# 555_module_throu.net
KiCad netlist of a schematic drawn in EAGLE
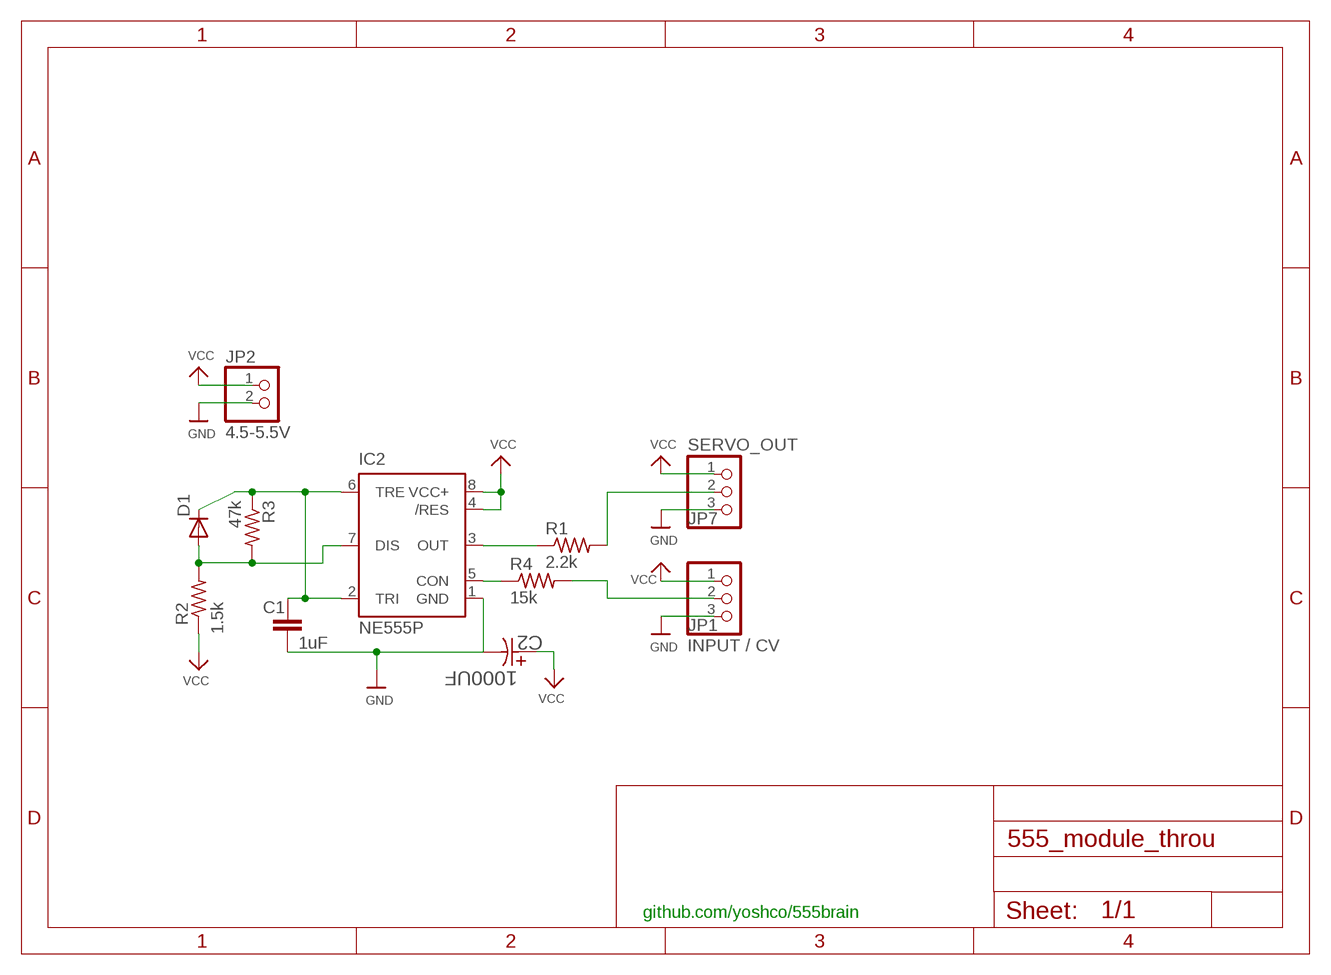
[diagram p0: schematic, sheet 1]

(export (version "E")
  (design (tool "Eeschema 10.0.6"))
  (components
    (comp (ref "C1")
      (value "1uF")
      (footprint "eagle-import:AXIAL-5MM")
      (libsource (lib "eagle-import") (part "CAP_"))
    )
    (comp (ref "C2")
      (value "1000UF")
      (footprint "eagle-import:CAPPR500-1000X3200")
      (fields (field (name "MPN") "EEUFK0J102") (field (name "TOLERANCE") "±20 %"))
      (libsource (lib "eagle-import") (part "EEU-P5.0FK0J102"))
    )
    (comp (ref "D1")
      (value "1N4004")
      (footprint "eagle-import:DO41-10")
      (libsource (lib "eagle-import") (part "1N4004"))
    )
    (comp (ref "IC2")
      (value "NE555P")
      (footprint "eagle-import:DIL-08")
      (fields (field (name "MF") "Arrow Electronics") (field (name "MPN") "NE555N"))
      (libsource (lib "eagle-import") (part "NE555P"))
    )
    (comp (ref "JP1")
      (value "INPUT / CV")
      (footprint "eagle-import:1X03")
      (libsource (lib "eagle-import") (part "PINHD-1X3"))
    )
    (comp (ref "JP2")
      (value "4.5-5.5V")
      (footprint "eagle-import:1X02_OVAL")
      (libsource (lib "eagle-import") (part "HEADER-1X2"))
    )
    (comp (ref "JP7")
      (value "SERVO_OUT")
      (footprint "eagle-import:1X03")
      (libsource (lib "eagle-import") (part "PINHD-1X3"))
    )
    (comp (ref "R1")
      (value "2.2k")
      (footprint "eagle-import:0204_7")
      (libsource (lib "eagle-import") (part "R-US_0204/7"))
    )
    (comp (ref "R2")
      (value "1.5k")
      (footprint "eagle-import:0204_7")
      (libsource (lib "eagle-import") (part "R-US_0204/7"))
    )
    (comp (ref "R3")
      (value "47k")
      (footprint "eagle-import:0204_7")
      (libsource (lib "eagle-import") (part "R-US_0204/7"))
    )
    (comp (ref "R4")
      (value "15k")
      (footprint "eagle-import:0204_7")
      (libsource (lib "eagle-import") (part "R-US_0204/7"))
    )
  )
  (nets
    (net (code "1") (name "GND") (class "Default")
      (node (ref "C1") (pin "P$2") (pinfunction "2_P$2") (pintype "passive"))
      (node (ref "C2") (pin "2") (pinfunction "2_2") (pintype "passive"))
      (node (ref "IC2") (pin "1") (pinfunction "GND_1") (pintype "power_in"))
      (node (ref "JP1") (pin "3") (pinfunction "3_3") (pintype "passive"))
      (node (ref "JP2") (pin "2") (pinfunction "2_2") (pintype "passive"))
      (node (ref "JP7") (pin "3") (pinfunction "3_3") (pintype "passive"))
    )
    (net (code "2") (name "Net-(C1-1)") (class "Default")
      (node (ref "C1") (pin "P$1") (pinfunction "1_P$1") (pintype "passive"))
      (node (ref "D1") (pin "C") (pinfunction "C_C") (pintype "passive"))
      (node (ref "IC2") (pin "2") (pinfunction "TRI_2") (pintype "input"))
      (node (ref "IC2") (pin "6") (pinfunction "TRE_6") (pintype "input"))
      (node (ref "R3") (pin "1") (pinfunction "1_1") (pintype "passive"))
    )
    (net (code "3") (name "Net-(IC2-CON)") (class "Default")
      (node (ref "IC2") (pin "5") (pinfunction "CON_5") (pintype "input"))
      (node (ref "R4") (pin "1") (pinfunction "1_1") (pintype "passive"))
    )
    (net (code "4") (name "Net-(IC2-DIS)") (class "Default")
      (node (ref "D1") (pin "A") (pinfunction "A_A") (pintype "passive"))
      (node (ref "IC2") (pin "7") (pinfunction "DIS_7") (pintype "input"))
      (node (ref "R2") (pin "2") (pinfunction "2_2") (pintype "passive"))
      (node (ref "R3") (pin "2") (pinfunction "2_2") (pintype "passive"))
    )
    (net (code "5") (name "Net-(IC2-OUT)") (class "Default")
      (node (ref "IC2") (pin "3") (pinfunction "OUT_3") (pintype "output"))
      (node (ref "R1") (pin "1") (pinfunction "1_1") (pintype "passive"))
    )
    (net (code "6") (name "Net-(JP1-Pad2)") (class "Default")
      (node (ref "JP1") (pin "2") (pinfunction "2_2") (pintype "passive"))
      (node (ref "R4") (pin "2") (pinfunction "2_2") (pintype "passive"))
    )
    (net (code "7") (name "Net-(JP7-Pad2)") (class "Default")
      (node (ref "JP7") (pin "2") (pinfunction "2_2") (pintype "passive"))
      (node (ref "R1") (pin "2") (pinfunction "2_2") (pintype "passive"))
    )
    (net (code "8") (name "VCC") (class "Default")
      (node (ref "C2") (pin "1") (pinfunction "1_1") (pintype "passive"))
      (node (ref "IC2") (pin "4") (pinfunction "/RES_4") (pintype "input"))
      (node (ref "IC2") (pin "8") (pinfunction "VCC+_8") (pintype "power_in"))
      (node (ref "JP1") (pin "1") (pinfunction "1_1") (pintype "passive"))
      (node (ref "JP2") (pin "1") (pinfunction "1_1") (pintype "passive"))
      (node (ref "JP7") (pin "1") (pinfunction "1_1") (pintype "passive"))
      (node (ref "R2") (pin "1") (pinfunction "1_1") (pintype "passive"))
    )
  )
)
